# CAN_TJA1050_Page1.net
KiCad netlist of a schematic drawn in Altium Designer
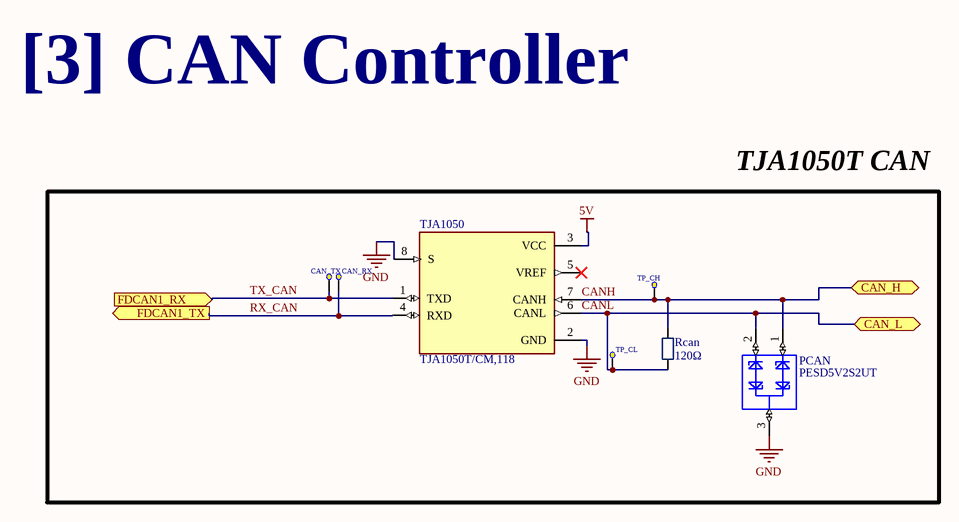
[diagram p0: CAN_TJA1050_Page1.SchDoc]

(export (version "E")
  (design (tool "Eeschema 10.0.6"))
  (components
    (comp (ref "CAN_RX")
      (value "~")
      (footprint "TestPoint")
      (libsource (lib "ealive_symbols") (part "TestPoint"))
    )
    (comp (ref "CAN_TX")
      (value "~")
      (footprint "TestPoint")
      (libsource (lib "ealive_symbols") (part "TestPoint"))
    )
    (comp (ref "PCAN")
      (value "PESD5V2S2UT")
      (footprint "PEDS1CAN")
      (description "ESD Protection Diodes / TVS Diodes PESD5V2S2UT/SOT23/TO-236AB")
      (fields (field (name "MF") "Nexperia USA") (field (name "MP") "PESD1CAN"))
      (libsource (lib "ealive_symbols") (part "PESDCAN"))
    )
    (comp (ref "Rcan")
      (value "120Ω")
      (footprint "Resistor_0805_Generic")
      (description "120Ω +-0.5%; 400V; 0805")
      (libsource (lib "ealive_symbols") (part "Resistor_0805"))
    )
    (comp (ref "TJA1050")
      (value "TJA1050T/CM,118")
      (footprint "TJA1050T")
      (description "1/1 Transceiver Half CANbus 8-SO")
      (fields (field (name "MF") "NXP USA"))
      (libsource (lib "ealive_symbols") (part "TJA1050T/CM,118"))
    )
    (comp (ref "TP_CH")
      (value "~")
      (footprint "TestPoint")
      (libsource (lib "ealive_symbols") (part "TestPoint"))
    )
    (comp (ref "TP_CL")
      (value "~")
      (footprint "TestPoint")
      (libsource (lib "ealive_symbols") (part "TestPoint"))
    )
  )
  (nets
    (net (code "1") (name "/CANH") (class "Default")
      (node (ref "PCAN") (pin "1") (pinfunction "1_1") (pintype "bidirectional"))
      (node (ref "Rcan") (pin "2") (pinfunction "2_2") (pintype "passive"))
      (node (ref "TJA1050") (pin "7") (pinfunction "CANH_7") (pintype "input"))
      (node (ref "TP_CH") (pin "1") (pinfunction "Test_Point_1") (pintype "passive"))
    )
    (net (code "2") (name "/CANL") (class "Default")
      (node (ref "PCAN") (pin "2") (pinfunction "2_2") (pintype "bidirectional"))
      (node (ref "Rcan") (pin "1") (pinfunction "1_1") (pintype "passive"))
      (node (ref "TJA1050") (pin "6") (pinfunction "CANL_6") (pintype "output"))
      (node (ref "TP_CL") (pin "1") (pinfunction "Test_Point_1") (pintype "passive"))
    )
    (net (code "3") (name "/RX_CAN") (class "Default")
      (node (ref "CAN_RX") (pin "1") (pinfunction "Test_Point_1") (pintype "passive"))
      (node (ref "TJA1050") (pin "4") (pinfunction "RXD_4") (pintype "bidirectional"))
    )
    (net (code "4") (name "/TX_CAN") (class "Default")
      (node (ref "CAN_TX") (pin "1") (pinfunction "Test_Point_1") (pintype "passive"))
      (node (ref "TJA1050") (pin "1") (pinfunction "TXD_1") (pintype "bidirectional"))
    )
    (net (code "5") (name "5V") (class "Default")
      (node (ref "TJA1050") (pin "3") (pinfunction "VCC_3") (pintype "power_in"))
    )
    (net (code "6") (name "GND") (class "Default")
      (node (ref "PCAN") (pin "3") (pinfunction "3_3") (pintype "bidirectional"))
      (node (ref "TJA1050") (pin "2") (pinfunction "GND_2") (pintype "power_in"))
      (node (ref "TJA1050") (pin "8") (pinfunction "S_8") (pintype "input"))
    )
    (net (code "7") (name "unconnected-(TJA1050-VREF-Pad5)") (class "Default")
      (node (ref "TJA1050") (pin "5") (pinfunction "VREF_5") (pintype "output+no_connect"))
    )
  )
)
